# ControlBox-3_1.net
KiCad netlist of a schematic drawn in EAGLE
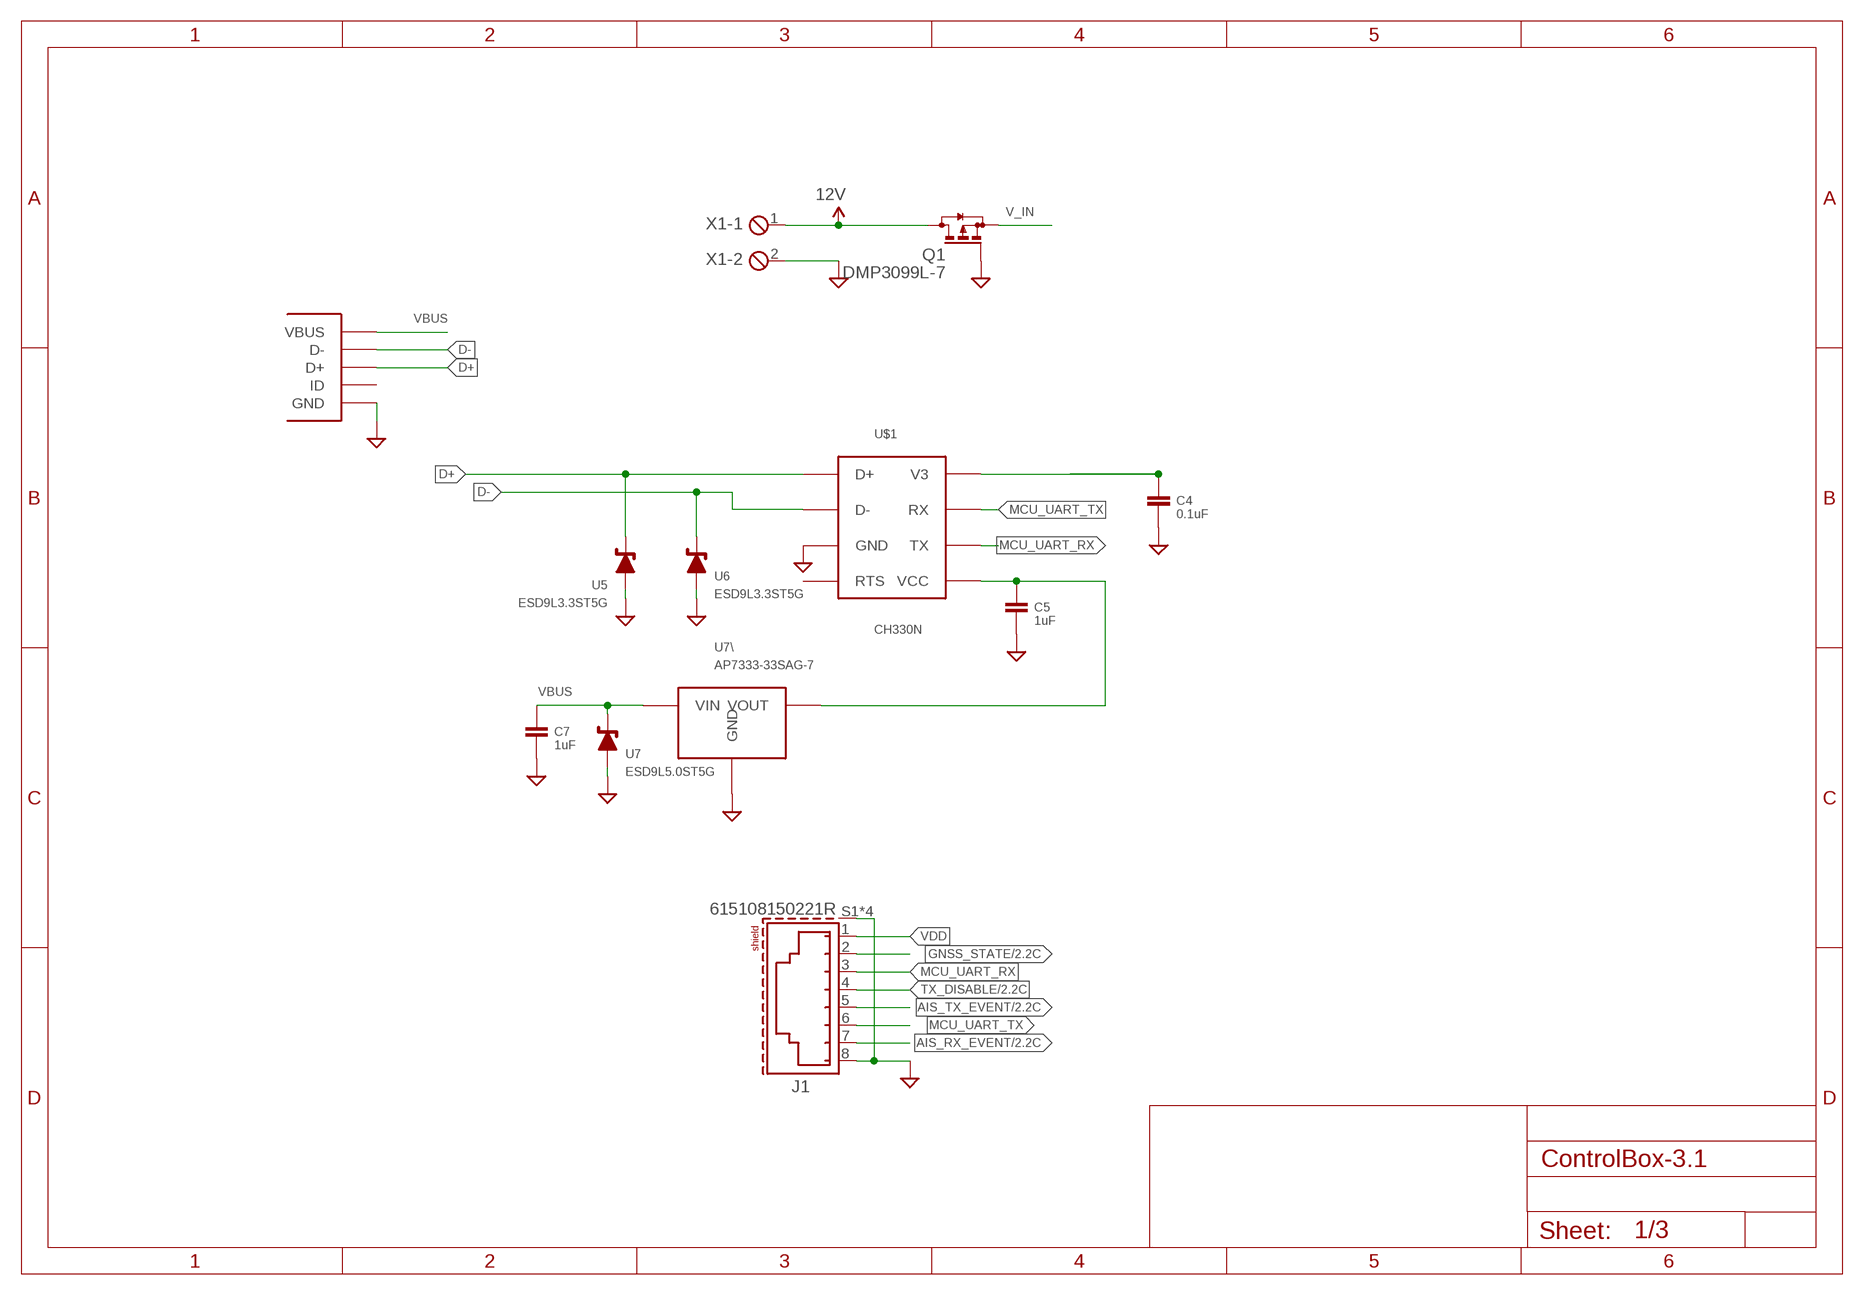
[diagram p0: schematic, sheet 1]
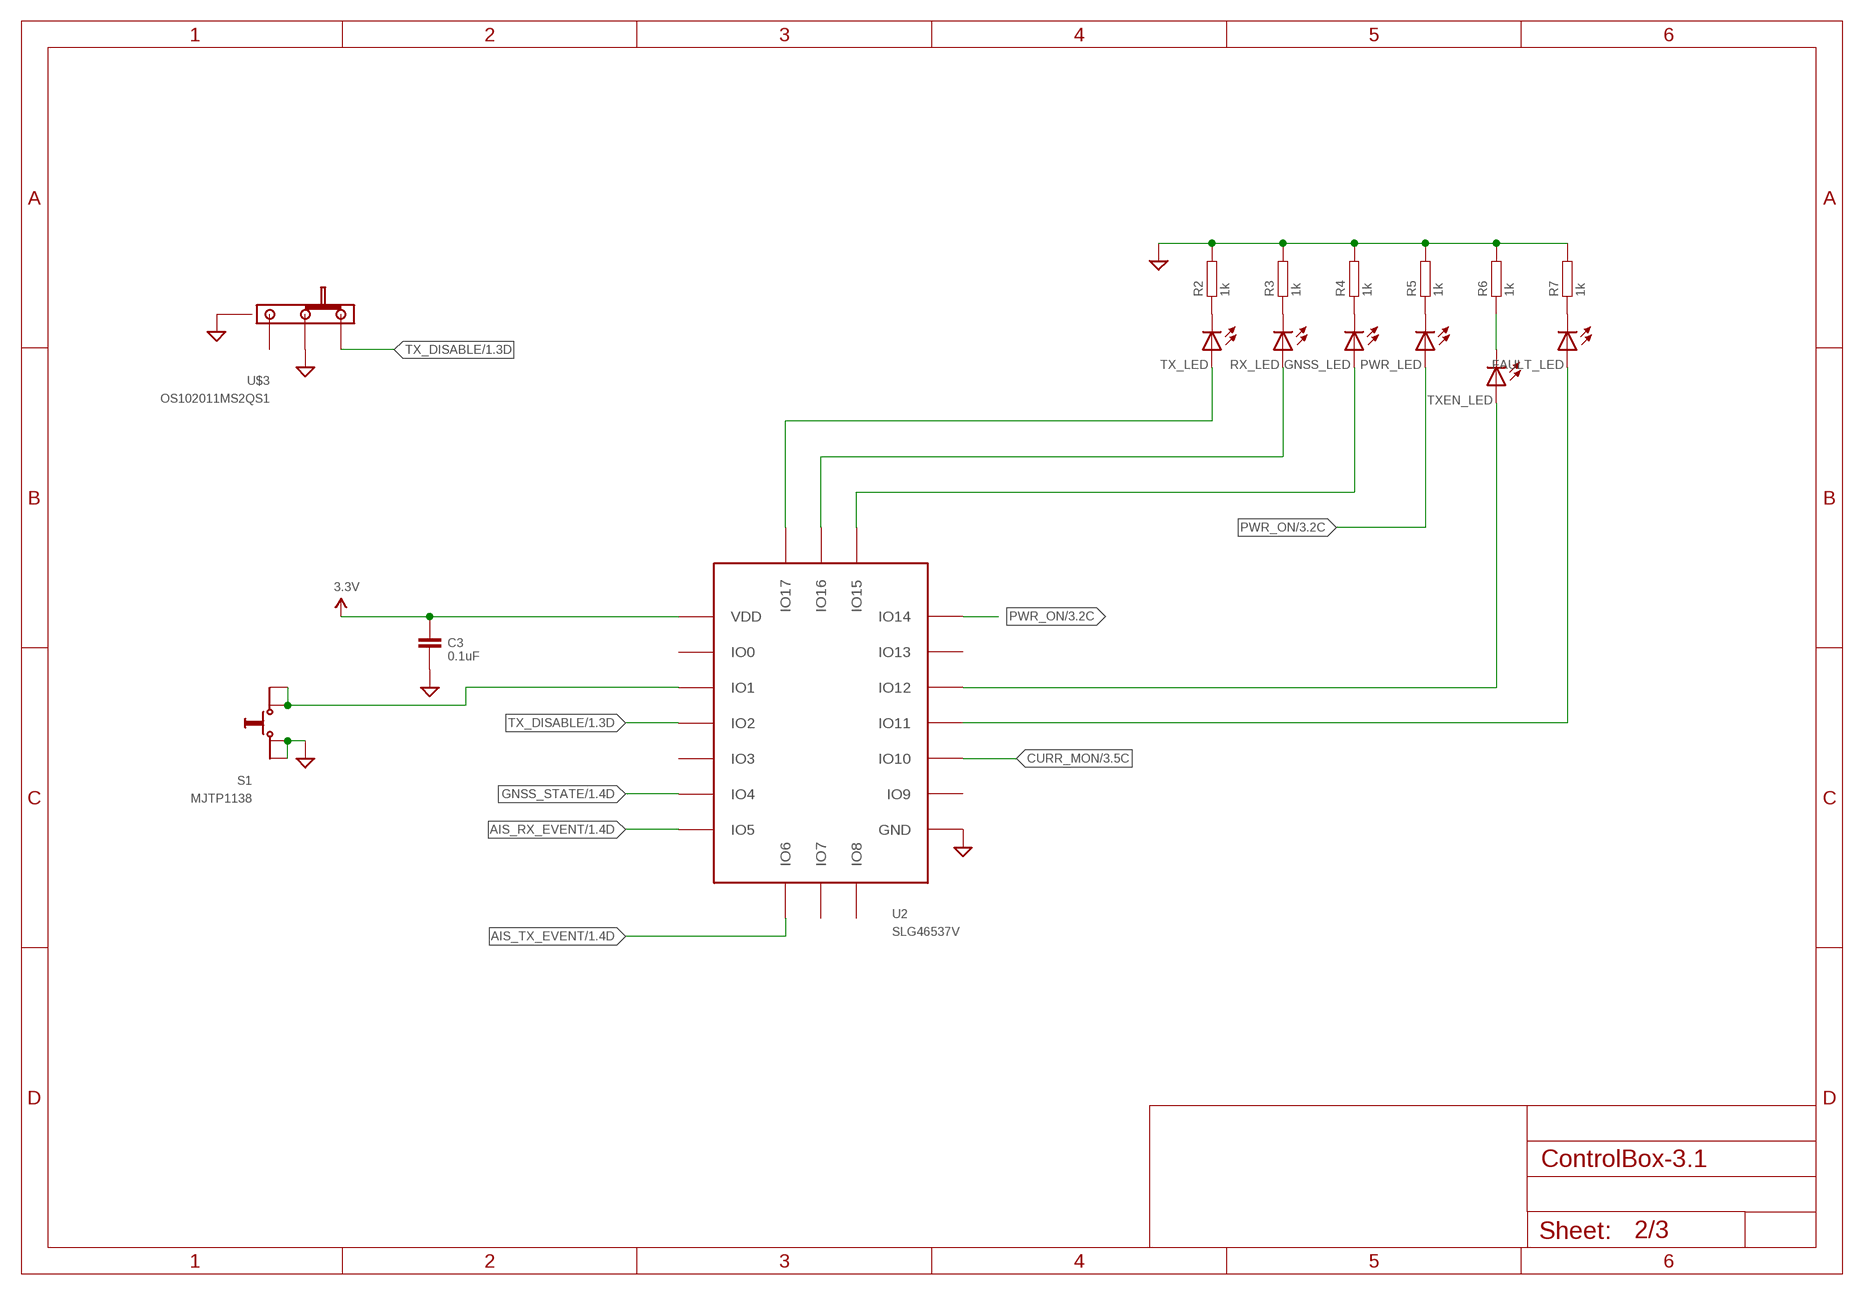
[diagram p1: schematic, sheet 2]
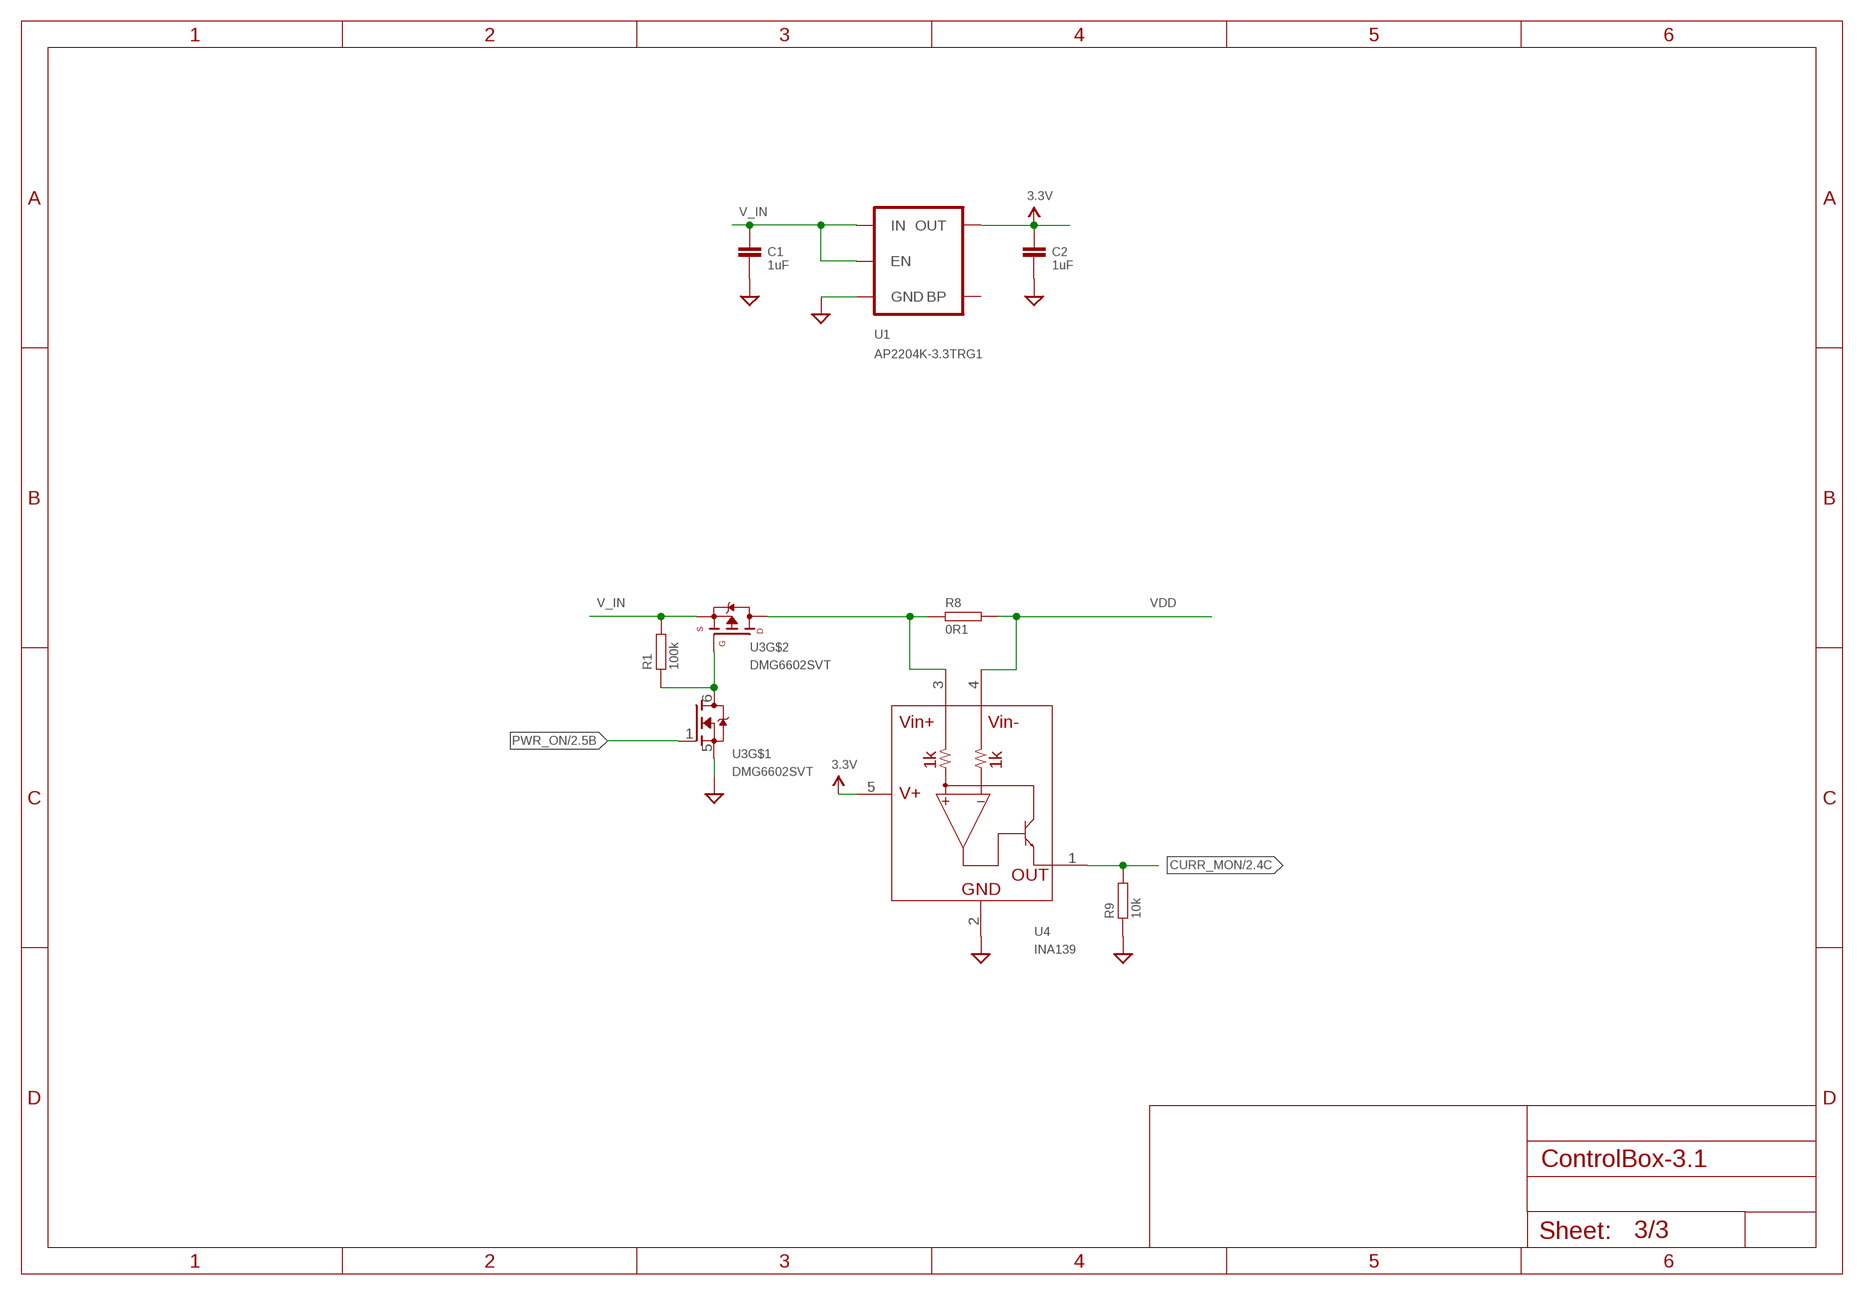
[diagram p2: schematic, sheet 3]

(export (version "E")
  (design (tool "Eeschema 10.0.6"))
  (components
    (comp (ref "C1")
      (value "1uF")
      (footprint "eagle-import:0603")
      (libsource (lib "eagle-import") (part "CAPACITOR0603"))
    )
    (comp (ref "C2")
      (value "1uF")
      (footprint "eagle-import:0603")
      (libsource (lib "eagle-import") (part "CAPACITOR0603"))
    )
    (comp (ref "R1")
      (value "100k")
      (footprint "eagle-import:0603")
      (libsource (lib "eagle-import") (part "RESISTOR0603"))
    )
    (comp (ref "R8")
      (value "0R1")
      (footprint "eagle-import:1206")
      (libsource (lib "eagle-import") (part "RESISTOR1206"))
    )
    (comp (ref "R9")
      (value "10k")
      (footprint "eagle-import:0603")
      (libsource (lib "eagle-import") (part "RESISTOR0603"))
    )
    (comp (ref "U1")
      (value "AP2204K-3.3TRG1")
      (footprint "eagle-import:SOT23-5")
      (libsource (lib "eagle-import") (part "V_REG_LDOSMD"))
    )
    (comp (ref "U3")
      (value "DMG6602SVT")
      (footprint "eagle-import:SOT23-6")
      (libsource (lib "eagle-import") (part "DMG6602SVT"))
    )
    (comp (ref "U4")
      (value "INA139")
      (footprint "eagle-import:SOT23-5")
      (libsource (lib "eagle-import") (part "INA169"))
    )
    (comp (ref "C3")
      (value "0.1uF")
      (footprint "eagle-import:0603")
      (libsource (lib "eagle-import") (part "CAPACITOR0603"))
    )
    (comp (ref "FAULT_LED")
      (value "LEDCHIPLED_0603")
      (footprint "eagle-import:CHIPLED_0603")
      (libsource (lib "eagle-import") (part "LEDCHIPLED_0603"))
    )
    (comp (ref "GNSS_LED")
      (value "LEDCHIPLED_0603")
      (footprint "eagle-import:CHIPLED_0603")
      (libsource (lib "eagle-import") (part "LEDCHIPLED_0603"))
    )
    (comp (ref "PWR_LED")
      (value "LEDCHIPLED_0603")
      (footprint "eagle-import:CHIPLED_0603")
      (libsource (lib "eagle-import") (part "LEDCHIPLED_0603"))
    )
    (comp (ref "R2")
      (value "1k")
      (footprint "eagle-import:0603")
      (libsource (lib "eagle-import") (part "RESISTOR0603"))
    )
    (comp (ref "R3")
      (value "1k")
      (footprint "eagle-import:0603")
      (libsource (lib "eagle-import") (part "RESISTOR0603"))
    )
    (comp (ref "R4")
      (value "1k")
      (footprint "eagle-import:0603")
      (libsource (lib "eagle-import") (part "RESISTOR0603"))
    )
    (comp (ref "R5")
      (value "1k")
      (footprint "eagle-import:0603")
      (libsource (lib "eagle-import") (part "RESISTOR0603"))
    )
    (comp (ref "R6")
      (value "1k")
      (footprint "eagle-import:0603")
      (libsource (lib "eagle-import") (part "RESISTOR0603"))
    )
    (comp (ref "R7")
      (value "1k")
      (footprint "eagle-import:0603")
      (libsource (lib "eagle-import") (part "RESISTOR0603"))
    )
    (comp (ref "RX_LED")
      (value "LEDCHIPLED_0603")
      (footprint "eagle-import:CHIPLED_0603")
      (libsource (lib "eagle-import") (part "LEDCHIPLED_0603"))
    )
    (comp (ref "S1")
      (value "MJTP1138")
      (footprint "eagle-import:MJTP1138")
      (libsource (lib "eagle-import") (part "MJTP1138"))
    )
    (comp (ref "TXEN_LED")
      (value "LEDCHIPLED_0603")
      (footprint "eagle-import:CHIPLED_0603")
      (libsource (lib "eagle-import") (part "LEDCHIPLED_0603"))
    )
    (comp (ref "TX_LED")
      (value "LEDCHIPLED_0603")
      (footprint "eagle-import:CHIPLED_0603")
      (libsource (lib "eagle-import") (part "LEDCHIPLED_0603"))
    )
    (comp (ref "U$3")
      (value "OS102011MS2QS1")
      (footprint "eagle-import:SPDT-PTH")
      (libsource (lib "eagle-import") (part "OS102011MS2QS1"))
    )
    (comp (ref "U2")
      (value "SLG46537V")
      (footprint "eagle-import:STQFN20L")
      (libsource (lib "eagle-import") (part "SLG46537"))
    )
    (comp (ref "C4")
      (value "0.1uF")
      (footprint "eagle-import:0603")
      (libsource (lib "eagle-import") (part "CAPACITOR0603"))
    )
    (comp (ref "C5")
      (value "1uF")
      (footprint "eagle-import:0603")
      (libsource (lib "eagle-import") (part "CAPACITOR0603"))
    )
    (comp (ref "C7")
      (value "1uF")
      (footprint "eagle-import:0603")
      (libsource (lib "eagle-import") (part "CAPACITOR0603"))
    )
    (comp (ref "J1")
      (value "615108150221R")
      (footprint "eagle-import:615108150221R")
      (fields (field (name "MF") "Würth Elektronik"))
      (libsource (lib "eagle-import") (part "615108150221R"))
    )
    (comp (ref "Q1")
      (value "DMP3099L-7")
      (footprint "eagle-import:SOT23")
      (libsource (lib "eagle-import") (part "BSS84"))
    )
    (comp (ref "U$1")
      (value "CH330N")
      (footprint "eagle-import:SOIC-8")
      (libsource (lib "eagle-import") (part "CH330N"))
    )
    (comp (ref "U$2")
      (value "MICRO_USB")
      (footprint "eagle-import:MICRO_USB")
      (libsource (lib "eagle-import") (part "MICRO_USB"))
    )
    (comp (ref "U5")
      (value "ESD9L3.3ST5G")
      (footprint "eagle-import:SODFL1006X40N")
      (fields (field (name "MF") "ON Semiconductor"))
      (libsource (lib "eagle-import") (part "ESD9L3.3ST5G"))
    )
    (comp (ref "U6")
      (value "ESD9L3.3ST5G")
      (footprint "eagle-import:SODFL1006X40N")
      (fields (field (name "MF") "ON Semiconductor"))
      (libsource (lib "eagle-import") (part "ESD9L3.3ST5G"))
    )
    (comp (ref "U7")
      (value "ESD9L5.0ST5G")
      (footprint "eagle-import:SODFL1006X40N")
      (fields (field (name "MF") "ON Semiconductor"))
      (libsource (lib "eagle-import") (part "ESD9L5.0ST5G"))
    )
    (comp (ref "U7\\")
      (value "AP7333-33SAG-7")
      (footprint "eagle-import:SOT-23")
      (libsource (lib "eagle-import") (part "AP7333-33SAG-7"))
    )
    (comp (ref "X1")
      (value "MPT2")
      (footprint "eagle-import:2POL254")
      (libsource (lib "eagle-import") (part "MPT2"))
    )
  )
  (nets
    (net (code "1") (name "3.3V") (class "Default")
      (node (ref "C2") (pin "P$1") (pinfunction "1_P$1") (pintype "passive"))
      (node (ref "C3") (pin "P$1") (pinfunction "1_P$1") (pintype "passive"))
      (node (ref "U1") (pin "5") (pinfunction "OUT_5") (pintype "passive"))
      (node (ref "U2") (pin "P$1") (pinfunction "VDD_P$1") (pintype "bidirectional"))
      (node (ref "U4") (pin "5") (pinfunction "V+_5") (pintype "bidirectional"))
    )
    (net (code "2") (name "12V") (class "Default")
      (node (ref "Q1") (pin "3") (pinfunction "D_3") (pintype "passive"))
      (node (ref "X1") (pin "1") (pinfunction "1_1") (pintype "passive"))
    )
    (net (code "3") (name "AIS_RX_EVENT") (class "Default")
      (node (ref "J1") (pin "7") (pinfunction "7_7") (pintype "passive"))
      (node (ref "U2") (pin "P$7") (pinfunction "IO5_P$7") (pintype "bidirectional"))
    )
    (net (code "4") (name "AIS_TX_EVENT") (class "Default")
      (node (ref "J1") (pin "5") (pinfunction "5_5") (pintype "passive"))
      (node (ref "U2") (pin "P$8") (pinfunction "IO6_P$8") (pintype "bidirectional"))
    )
    (net (code "5") (name "CURR_MON") (class "Default")
      (node (ref "R9") (pin "P$2") (pinfunction "P$2_P$2") (pintype "passive"))
      (node (ref "U2") (pin "P$13") (pinfunction "IO10_P$13") (pintype "bidirectional"))
      (node (ref "U4") (pin "1") (pinfunction "OUT_1") (pintype "bidirectional"))
    )
    (net (code "6") (name "D+") (class "Default")
      (node (ref "U$1") (pin "1") (pinfunction "D+_1") (pintype "bidirectional"))
      (node (ref "U$2") (pin "D+") (pinfunction "D+_D+") (pintype "bidirectional"))
      (node (ref "U5") (pin "1") (pinfunction "P$1_1") (pintype "bidirectional"))
    )
    (net (code "7") (name "D-") (class "Default")
      (node (ref "U$1") (pin "2") (pinfunction "D-_2") (pintype "bidirectional"))
      (node (ref "U$2") (pin "D-") (pinfunction "D-_D-") (pintype "bidirectional"))
      (node (ref "U6") (pin "1") (pinfunction "P$1_1") (pintype "bidirectional"))
    )
    (net (code "8") (name "GND") (class "Default")
      (node (ref "C1") (pin "P$2") (pinfunction "2_P$2") (pintype "passive"))
      (node (ref "C2") (pin "P$2") (pinfunction "2_P$2") (pintype "passive"))
      (node (ref "C3") (pin "P$2") (pinfunction "2_P$2") (pintype "passive"))
      (node (ref "C4") (pin "P$2") (pinfunction "2_P$2") (pintype "passive"))
      (node (ref "C5") (pin "P$2") (pinfunction "2_P$2") (pintype "passive"))
      (node (ref "C7") (pin "P$2") (pinfunction "2_P$2") (pintype "passive"))
      (node (ref "J1") (pin "8") (pinfunction "8_8") (pintype "passive"))
      (node (ref "J1") (pin "S1") (pinfunction "SHIELD_S1") (pintype "passive"))
      (node (ref "J1") (pin "S2") (pinfunction "SHIELD_S2") (pintype "passive"))
      (node (ref "J1") (pin "S3") (pinfunction "SHIELD_S3") (pintype "passive"))
      (node (ref "J1") (pin "S4") (pinfunction "SHIELD_S4") (pintype "passive"))
      (node (ref "Q1") (pin "1") (pinfunction "G_1") (pintype "passive"))
      (node (ref "R2") (pin "P$2") (pinfunction "P$2_P$2") (pintype "passive"))
      (node (ref "R3") (pin "P$2") (pinfunction "P$2_P$2") (pintype "passive"))
      (node (ref "R4") (pin "P$2") (pinfunction "P$2_P$2") (pintype "passive"))
      (node (ref "R5") (pin "P$2") (pinfunction "P$2_P$2") (pintype "passive"))
      (node (ref "R6") (pin "P$2") (pinfunction "P$2_P$2") (pintype "passive"))
      (node (ref "R7") (pin "P$2") (pinfunction "P$2_P$2") (pintype "passive"))
      (node (ref "R9") (pin "P$1") (pinfunction "P$1_P$1") (pintype "passive"))
      (node (ref "S1") (pin "P$2") (pinfunction "B_P$2") (pintype "passive"))
      (node (ref "S1") (pin "P$3") (pinfunction "B_P$3") (pintype "passive"))
      (node (ref "U$1") (pin "3") (pinfunction "GND_3") (pintype "bidirectional"))
      (node (ref "U$2") (pin "GND") (pinfunction "GND_GND") (pintype "bidirectional"))
      (node (ref "U$2") (pin "MT1") (pinfunction "GND_MT1") (pintype "bidirectional"))
      (node (ref "U$2") (pin "MT2") (pinfunction "GND_MT2") (pintype "bidirectional"))
      (node (ref "U$2") (pin "P$1") (pinfunction "GND_P$1") (pintype "bidirectional"))
      (node (ref "U$2") (pin "P$2") (pinfunction "GND_P$2") (pintype "bidirectional"))
      (node (ref "U$3") (pin "P$2") (pinfunction "2_P$2") (pintype "bidirectional"))
      (node (ref "U$3") (pin "P$4") (pinfunction "SHLD_P$4") (pintype "bidirectional"))
      (node (ref "U$3") (pin "P$5") (pinfunction "SHLD_P$5") (pintype "bidirectional"))
      (node (ref "U1") (pin "2") (pinfunction "GND_2") (pintype "input"))
      (node (ref "U2") (pin "P$11") (pinfunction "GND_P$11") (pintype "bidirectional"))
      (node (ref "U3") (pin "5") (pinfunction "S_5") (pintype "bidirectional"))
      (node (ref "U4") (pin "2") (pinfunction "GND_2") (pintype "bidirectional"))
      (node (ref "U5") (pin "2") (pinfunction "P$2_2") (pintype "bidirectional"))
      (node (ref "U6") (pin "2") (pinfunction "P$2_2") (pintype "bidirectional"))
      (node (ref "U7") (pin "2") (pinfunction "P$2_2") (pintype "bidirectional"))
      (node (ref "U7\\") (pin "3") (pinfunction "GND_3") (pintype "bidirectional"))
      (node (ref "X1") (pin "2") (pinfunction "1_2") (pintype "passive"))
    )
    (net (code "9") (name "GNSS_STATE") (class "Default")
      (node (ref "J1") (pin "2") (pinfunction "2_2") (pintype "passive"))
      (node (ref "U2") (pin "P$6") (pinfunction "IO4_P$6") (pintype "bidirectional"))
    )
    (net (code "10") (name "MCU_UART_RX") (class "Default")
      (node (ref "J1") (pin "3") (pinfunction "3_3") (pintype "passive"))
      (node (ref "U$1") (pin "6") (pinfunction "TX_6") (pintype "bidirectional"))
    )
    (net (code "11") (name "MCU_UART_TX") (class "Default")
      (node (ref "J1") (pin "6") (pinfunction "6_6") (pintype "passive"))
      (node (ref "U$1") (pin "7") (pinfunction "RX_7") (pintype "bidirectional"))
    )
    (net (code "12") (name "Net-(C4-1)") (class "Default")
      (node (ref "C4") (pin "P$1") (pinfunction "1_P$1") (pintype "passive"))
      (node (ref "U$1") (pin "8") (pinfunction "V3_8") (pintype "bidirectional"))
    )
    (net (code "13") (name "Net-(C5-1)") (class "Default")
      (node (ref "C5") (pin "P$1") (pinfunction "1_P$1") (pintype "passive"))
      (node (ref "U$1") (pin "5") (pinfunction "VCC_5") (pintype "bidirectional"))
      (node (ref "U7\\") (pin "2") (pinfunction "VOUT_2") (pintype "bidirectional"))
    )
    (net (code "14") (name "Net-(FAULT_LED-PadC)") (class "Default")
      (node (ref "FAULT_LED") (pin "C") (pinfunction "C_C") (pintype "passive"))
      (node (ref "R7") (pin "P$1") (pinfunction "P$1_P$1") (pintype "passive"))
    )
    (net (code "15") (name "Net-(GNSS_LED-PadC)") (class "Default")
      (node (ref "GNSS_LED") (pin "C") (pinfunction "C_C") (pintype "passive"))
      (node (ref "R4") (pin "P$1") (pinfunction "P$1_P$1") (pintype "passive"))
    )
    (net (code "16") (name "Net-(PWR_LED-PadC)") (class "Default")
      (node (ref "PWR_LED") (pin "C") (pinfunction "C_C") (pintype "passive"))
      (node (ref "R5") (pin "P$1") (pinfunction "P$1_P$1") (pintype "passive"))
    )
    (net (code "17") (name "Net-(R2-PadP$1)") (class "Default")
      (node (ref "R2") (pin "P$1") (pinfunction "P$1_P$1") (pintype "passive"))
      (node (ref "TX_LED") (pin "C") (pinfunction "C_C") (pintype "passive"))
    )
    (net (code "18") (name "Net-(R3-PadP$1)") (class "Default")
      (node (ref "R3") (pin "P$1") (pinfunction "P$1_P$1") (pintype "passive"))
      (node (ref "RX_LED") (pin "C") (pinfunction "C_C") (pintype "passive"))
    )
    (net (code "19") (name "Net-(R6-PadP$1)") (class "Default")
      (node (ref "R6") (pin "P$1") (pinfunction "P$1_P$1") (pintype "passive"))
      (node (ref "TXEN_LED") (pin "C") (pinfunction "C_C") (pintype "passive"))
    )
    (net (code "20") (name "Net-(U2-IO1)") (class "Default")
      (node (ref "S1") (pin "P$1") (pinfunction "A_P$1") (pintype "passive"))
      (node (ref "S1") (pin "P$4") (pinfunction "A_P$4") (pintype "passive"))
      (node (ref "U2") (pin "P$3") (pinfunction "IO1_P$3") (pintype "bidirectional"))
    )
    (net (code "21") (name "Net-(U2-IO11)") (class "Default")
      (node (ref "FAULT_LED") (pin "A") (pinfunction "A_A") (pintype "passive"))
      (node (ref "U2") (pin "P$14") (pinfunction "IO11_P$14") (pintype "bidirectional"))
    )
    (net (code "22") (name "Net-(U2-IO12)") (class "Default")
      (node (ref "TXEN_LED") (pin "A") (pinfunction "A_A") (pintype "passive"))
      (node (ref "U2") (pin "P$15") (pinfunction "IO12_P$15") (pintype "bidirectional"))
    )
    (net (code "23") (name "Net-(U2-IO15)") (class "Default")
      (node (ref "GNSS_LED") (pin "A") (pinfunction "A_A") (pintype "passive"))
      (node (ref "U2") (pin "P$18") (pinfunction "IO15_P$18") (pintype "bidirectional"))
    )
    (net (code "24") (name "Net-(U2-IO16)") (class "Default")
      (node (ref "RX_LED") (pin "A") (pinfunction "A_A") (pintype "passive"))
      (node (ref "U2") (pin "P$19") (pinfunction "IO16_P$19") (pintype "bidirectional"))
    )
    (net (code "25") (name "Net-(U2-IO17)") (class "Default")
      (node (ref "TX_LED") (pin "A") (pinfunction "A_A") (pintype "passive"))
      (node (ref "U2") (pin "P$20") (pinfunction "IO17_P$20") (pintype "bidirectional"))
    )
    (net (code "26") (name "Net-(U3A-D)") (class "Default")
      (node (ref "R1") (pin "P$1") (pinfunction "P$1_P$1") (pintype "passive"))
      (node (ref "U3") (pin "3") (pinfunction "G_3") (pintype "passive"))
      (node (ref "U3") (pin "6") (pinfunction "D_6") (pintype "bidirectional"))
    )
    (net (code "27") (name "Net-(U3B-D)") (class "Default")
      (node (ref "R8") (pin "P$1") (pinfunction "P$1_P$1") (pintype "passive"))
      (node (ref "U3") (pin "4") (pinfunction "D_4") (pintype "passive"))
      (node (ref "U4") (pin "3") (pinfunction "VIN+_3") (pintype "bidirectional"))
    )
    (net (code "28") (name "PWR_ON") (class "Default")
      (node (ref "PWR_LED") (pin "A") (pinfunction "A_A") (pintype "passive"))
      (node (ref "U2") (pin "P$17") (pinfunction "IO14_P$17") (pintype "bidirectional"))
      (node (ref "U3") (pin "1") (pinfunction "G_1") (pintype "bidirectional"))
    )
    (net (code "29") (name "TX_DISABLE") (class "Default")
      (node (ref "J1") (pin "4") (pinfunction "4_4") (pintype "passive"))
      (node (ref "U$3") (pin "P$1") (pinfunction "1_P$1") (pintype "bidirectional"))
      (node (ref "U2") (pin "P$4") (pinfunction "IO2_P$4") (pintype "bidirectional"))
    )
    (net (code "30") (name "VBUS") (class "Default")
      (node (ref "C7") (pin "P$1") (pinfunction "1_P$1") (pintype "passive"))
      (node (ref "U$2") (pin "VBUS") (pinfunction "VBUS_VBUS") (pintype "bidirectional"))
      (node (ref "U7") (pin "1") (pinfunction "P$1_1") (pintype "bidirectional"))
      (node (ref "U7\\") (pin "1") (pinfunction "VIN_1") (pintype "bidirectional"))
    )
    (net (code "31") (name "VDD") (class "Default")
      (node (ref "J1") (pin "1") (pinfunction "1_1") (pintype "passive"))
      (node (ref "R8") (pin "P$2") (pinfunction "P$2_P$2") (pintype "passive"))
      (node (ref "U4") (pin "4") (pinfunction "VIN-_4") (pintype "bidirectional"))
    )
    (net (code "32") (name "V_IN") (class "Default")
      (node (ref "C1") (pin "P$1") (pinfunction "1_P$1") (pintype "passive"))
      (node (ref "Q1") (pin "2") (pinfunction "S_2") (pintype "passive"))
      (node (ref "R1") (pin "P$2") (pinfunction "P$2_P$2") (pintype "passive"))
      (node (ref "U1") (pin "1") (pinfunction "IN_1") (pintype "input"))
      (node (ref "U1") (pin "3") (pinfunction "EN_3") (pintype "input"))
      (node (ref "U3") (pin "2") (pinfunction "S_2") (pintype "passive"))
    )
    (net (code "33") (name "unconnected-(U$1-RTS-Pad4)") (class "Default")
      (node (ref "U$1") (pin "4") (pinfunction "RTS_4") (pintype "bidirectional"))
    )
    (net (code "34") (name "unconnected-(U$2-PadID)") (class "Default")
      (node (ref "U$2") (pin "ID") (pinfunction "ID_ID") (pintype "bidirectional"))
    )
    (net (code "35") (name "unconnected-(U$3-3-PadP$3)") (class "Default")
      (node (ref "U$3") (pin "P$3") (pinfunction "3_P$3") (pintype "bidirectional"))
    )
    (net (code "36") (name "unconnected-(U1-BP-Pad4)") (class "Default")
      (node (ref "U1") (pin "4") (pinfunction "BP_4") (pintype "input"))
    )
    (net (code "37") (name "unconnected-(U2-IO0-PadP$2)") (class "Default")
      (node (ref "U2") (pin "P$2") (pinfunction "IO0_P$2") (pintype "bidirectional"))
    )
    (net (code "38") (name "unconnected-(U2-IO3-PadP$5)") (class "Default")
      (node (ref "U2") (pin "P$5") (pinfunction "IO3_P$5") (pintype "bidirectional"))
    )
    (net (code "39") (name "unconnected-(U2-IO7-PadP$9)") (class "Default")
      (node (ref "U2") (pin "P$9") (pinfunction "IO7_P$9") (pintype "bidirectional"))
    )
    (net (code "40") (name "unconnected-(U2-IO8-PadP$10)") (class "Default")
      (node (ref "U2") (pin "P$10") (pinfunction "IO8_P$10") (pintype "bidirectional"))
    )
    (net (code "41") (name "unconnected-(U2-IO9-PadP$12)") (class "Default")
      (node (ref "U2") (pin "P$12") (pinfunction "IO9_P$12") (pintype "bidirectional"))
    )
    (net (code "42") (name "unconnected-(U2-IO13-PadP$16)") (class "Default")
      (node (ref "U2") (pin "P$16") (pinfunction "IO13_P$16") (pintype "bidirectional"))
    )
  )
)
